# GPIO_Pullups_Pulldowns.net
KiCad netlist of a schematic drawn in Altium Designer
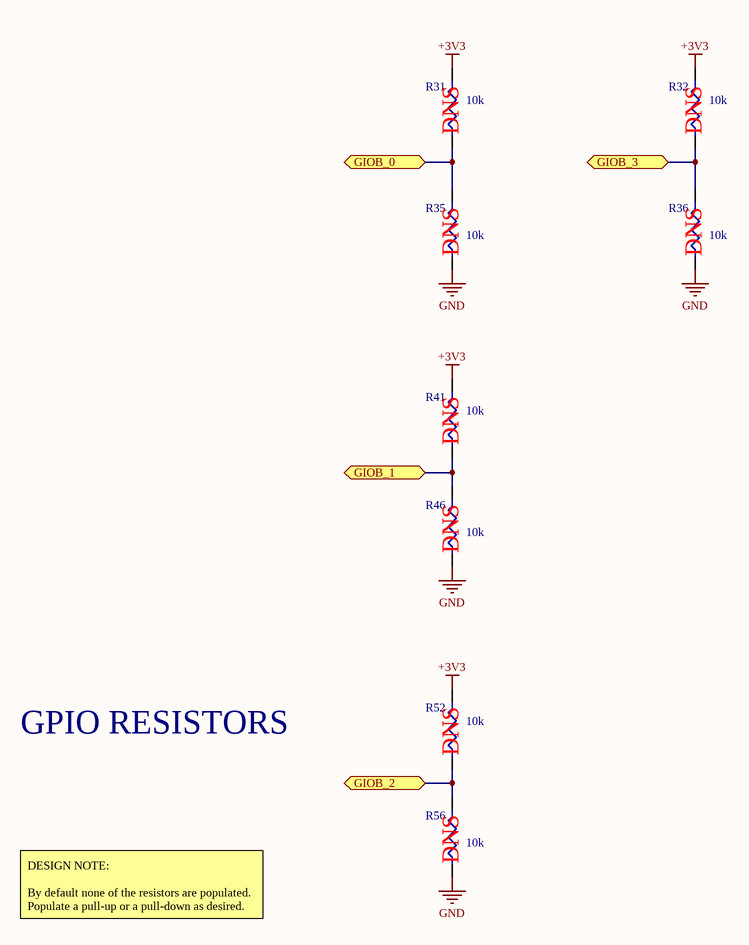
[diagram p0: GPIO_Pullups_Pulldowns.SchDoc]

(export (version "E")
  (design (tool "Eeschema 10.0.6"))
  (components
    (comp (ref "R31")
      (value "10k")
      (footprint "R0805")
      (description "RES SMD 10K OHM 1% 1/8W 0805")
      (fields
        (field (name "MANUFACTURER") "Yageo Phycomp")
        (field (name "MANUFACTURER PART NUMBER") "RC0805FR-071KL")
      )
      (libsource (lib "PHANTOM_LIBRARY") (part "RC0805FR-071KL"))
    )
    (comp (ref "R32")
      (value "10k")
      (footprint "R0805")
      (description "RES SMD 10K OHM 1% 1/8W 0805")
      (fields
        (field (name "MANUFACTURER") "Yageo Phycomp")
        (field (name "MANUFACTURER PART NUMBER") "RC0805FR-071KL")
      )
      (libsource (lib "PHANTOM_LIBRARY") (part "RC0805FR-071KL"))
    )
    (comp (ref "R35")
      (value "10k")
      (footprint "R0805")
      (description "RES SMD 10K OHM 1% 1/8W 0805")
      (fields
        (field (name "MANUFACTURER") "Yageo Phycomp")
        (field (name "MANUFACTURER PART NUMBER") "RC0805FR-071KL")
      )
      (libsource (lib "PHANTOM_LIBRARY") (part "RC0805FR-071KL"))
    )
    (comp (ref "R36")
      (value "10k")
      (footprint "R0805")
      (description "RES SMD 10K OHM 1% 1/8W 0805")
      (fields
        (field (name "MANUFACTURER") "Yageo Phycomp")
        (field (name "MANUFACTURER PART NUMBER") "RC0805FR-071KL")
      )
      (libsource (lib "PHANTOM_LIBRARY") (part "RC0805FR-071KL"))
    )
    (comp (ref "R41")
      (value "10k")
      (footprint "R0805")
      (description "RES SMD 10K OHM 1% 1/8W 0805")
      (fields
        (field (name "MANUFACTURER") "Yageo Phycomp")
        (field (name "MANUFACTURER PART NUMBER") "RC0805FR-071KL")
      )
      (libsource (lib "PHANTOM_LIBRARY") (part "RC0805FR-071KL"))
    )
    (comp (ref "R46")
      (value "10k")
      (footprint "R0805")
      (description "RES SMD 10K OHM 1% 1/8W 0805")
      (fields
        (field (name "MANUFACTURER") "Yageo Phycomp")
        (field (name "MANUFACTURER PART NUMBER") "RC0805FR-071KL")
      )
      (libsource (lib "PHANTOM_LIBRARY") (part "RC0805FR-071KL"))
    )
    (comp (ref "R52")
      (value "10k")
      (footprint "R0805")
      (description "RES SMD 10K OHM 1% 1/8W 0805")
      (fields
        (field (name "MANUFACTURER") "Yageo Phycomp")
        (field (name "MANUFACTURER PART NUMBER") "RC0805FR-071KL")
      )
      (libsource (lib "PHANTOM_LIBRARY") (part "RC0805FR-071KL"))
    )
    (comp (ref "R56")
      (value "10k")
      (footprint "R0805")
      (description "RES SMD 10K OHM 1% 1/8W 0805")
      (fields
        (field (name "MANUFACTURER") "Yageo Phycomp")
        (field (name "MANUFACTURER PART NUMBER") "RC0805FR-071KL")
      )
      (libsource (lib "PHANTOM_LIBRARY") (part "RC0805FR-071KL"))
    )
  )
  (nets
    (net (code "1") (name "+3V3") (class "Default")
      (node (ref "R31") (pin "2") (pinfunction "2_2") (pintype "passive"))
      (node (ref "R32") (pin "2") (pinfunction "2_2") (pintype "passive"))
      (node (ref "R41") (pin "2") (pinfunction "2_2") (pintype "passive"))
      (node (ref "R52") (pin "2") (pinfunction "2_2") (pintype "passive"))
    )
    (net (code "2") (name "/GIOB_0") (class "Default")
      (node (ref "R31") (pin "1") (pinfunction "1_1") (pintype "passive"))
      (node (ref "R35") (pin "2") (pinfunction "2_2") (pintype "passive"))
    )
    (net (code "3") (name "/GIOB_1") (class "Default")
      (node (ref "R41") (pin "1") (pinfunction "1_1") (pintype "passive"))
      (node (ref "R46") (pin "2") (pinfunction "2_2") (pintype "passive"))
    )
    (net (code "4") (name "/GIOB_2") (class "Default")
      (node (ref "R52") (pin "1") (pinfunction "1_1") (pintype "passive"))
      (node (ref "R56") (pin "2") (pinfunction "2_2") (pintype "passive"))
    )
    (net (code "5") (name "/GIOB_3") (class "Default")
      (node (ref "R32") (pin "1") (pinfunction "1_1") (pintype "passive"))
      (node (ref "R36") (pin "2") (pinfunction "2_2") (pintype "passive"))
    )
    (net (code "6") (name "GND") (class "Default")
      (node (ref "R35") (pin "1") (pinfunction "1_1") (pintype "passive"))
      (node (ref "R36") (pin "1") (pinfunction "1_1") (pintype "passive"))
      (node (ref "R46") (pin "1") (pinfunction "1_1") (pintype "passive"))
      (node (ref "R56") (pin "1") (pinfunction "1_1") (pintype "passive"))
    )
  )
)
